# VibrationACQ.net
KiCad netlist of a schematic drawn in Altium Designer
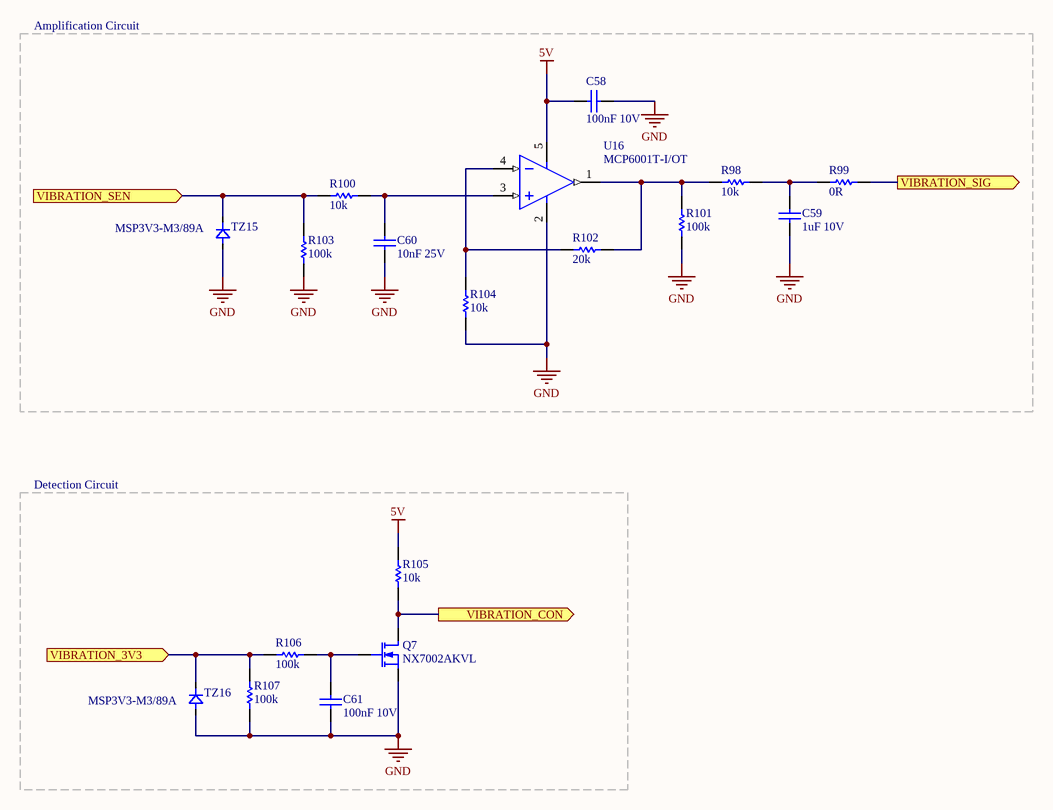
[diagram p0: VibrationACQ.SchDoc]

(export (version "E")
  (design (tool "Eeschema 10.0.6"))
  (components
    (comp (ref "C58")
      (value "100nF 10V")
      (footprint "0402")
      (description "Capacitor")
      (fields (field (name "PARTNUMBER") "CAP.100n.10V.20%.SMD.0402") (field (name "MANUFACTURER") "Wurth"))
      (libsource (lib "IntLib") (part "Cap"))
    )
    (comp (ref "C59")
      (value "1uF 10V")
      (footprint "C0805")
      (description "Capacitor")
      (fields (field (name "PARTNUMBER") "CAP.1u.10V.10%.SMD.0805") (field (name "MANUFACTURER") "Vishay"))
      (libsource (lib "IntLib") (part "Cap"))
    )
    (comp (ref "C60")
      (value "10nF 25V")
      (footprint "1608[0603]")
      (description "Capacitor")
      (fields (field (name "PARTNUMBER") "CAP.10n.25V.10%.SMD.0603") (field (name "MANUFACTURER") "Wurth"))
      (libsource (lib "IntLib") (part "Cap"))
    )
    (comp (ref "C61")
      (value "100nF 10V")
      (footprint "0402")
      (description "Capacitor")
      (fields (field (name "PARTNUMBER") "CAP.100n.10V.20%.SMD.0402") (field (name "MANUFACTURER") "Wurth"))
      (libsource (lib "IntLib") (part "Cap"))
    )
    (comp (ref "Q7")
      (value "NX7002AKVL")
      (footprint "SOT23_M")
      (description "Small Signal MOSFET 60 V, 310 mA, Single, N−Channel, SOT−23")
      (fields (field (name "MANUFACTURER") "Nexperia"))
      (libsource (lib "IntLib") (part "NX7002AKVL"))
    )
    (comp (ref "R98")
      (value "10k")
      (footprint "6-0805_M")
      (description "Resistor")
      (fields (field (name "PARTNUMBER") "RES.10K.1/8W.5%.SMD.0805") (field (name "MANUFACTURER") "Yageo"))
      (libsource (lib "IntLib") (part "Res"))
    )
    (comp (ref "R99")
      (value "0R")
      (footprint "6-0805_M")
      (description "Resistor")
      (fields (field (name "PARTNUMBER") "RES.0R.1/8W.5%.SMD.0805") (field (name "MANUFACTURER") "Vishay"))
      (libsource (lib "IntLib") (part "Res"))
    )
    (comp (ref "R100")
      (value "10k")
      (footprint "6-0805_M")
      (description "Resistor")
      (fields (field (name "PARTNUMBER") "RES.10K.1/8W.5%.SMD.0805") (field (name "MANUFACTURER") "Yageo"))
      (libsource (lib "IntLib") (part "Res"))
    )
    (comp (ref "R101")
      (value "100k")
      (footprint "6-0805_M")
      (description "Resistor")
      (fields (field (name "PARTNUMBER") "RES.100K.1/8W.5%.SMD.0805") (field (name "MANUFACTURER") "Yageo"))
      (libsource (lib "IntLib") (part "Res"))
    )
    (comp (ref "R102")
      (value "20k")
      (footprint "6-0805_M")
      (description "Resistor")
      (fields (field (name "PARTNUMBER") "RES.20K.1/8W.1%.SMD.0805") (field (name "MANUFACTURER") "Vishay"))
      (libsource (lib "IntLib") (part "Res"))
    )
    (comp (ref "R103")
      (value "100k")
      (footprint "6-0805_M")
      (description "Resistor")
      (fields (field (name "PARTNUMBER") "RES.100k.1/8W.5%.SMD.0805") (field (name "MANUFACTURER") "Bourns"))
      (libsource (lib "IntLib") (part "Res"))
    )
    (comp (ref "R104")
      (value "10k")
      (footprint "6-0805_M")
      (description "Resistor")
      (fields (field (name "PARTNUMBER") "RES.10K.1/8W.5%.SMD.0805") (field (name "MANUFACTURER") "Yageo"))
      (libsource (lib "IntLib") (part "Res"))
    )
    (comp (ref "R105")
      (value "10k")
      (footprint "6-0805_M")
      (description "Resistor")
      (fields (field (name "PARTNUMBER") "RES.10K.1/8W.5%.SMD.0805") (field (name "MANUFACTURER") "Yageo"))
      (libsource (lib "IntLib") (part "Res"))
    )
    (comp (ref "R106")
      (value "100k")
      (footprint "6-0805_M")
      (description "Resistor")
      (fields (field (name "PARTNUMBER") "RES.100K.1/8W.5%.SMD.0805") (field (name "MANUFACTURER") "Yageo"))
      (libsource (lib "IntLib") (part "Res"))
    )
    (comp (ref "R107")
      (value "100k")
      (footprint "6-0805_M")
      (description "Resistor")
      (fields (field (name "PARTNUMBER") "RES.100k.1/8W.5%.SMD.0805") (field (name "MANUFACTURER") "Bourns"))
      (libsource (lib "IntLib") (part "Res"))
    )
    (comp (ref "TZ15")
      (value "MSP3V3-M3/89A")
      (footprint "DO-219AD")
      (description "ESD Suppressors / TVS Diodes 100W 3.3V Unidirect")
      (fields (field (name "MANUFACTURER") "Vishay"))
      (libsource (lib "IntLib") (part "MSP3V3-M3/89A"))
    )
    (comp (ref "TZ16")
      (value "MSP3V3-M3/89A")
      (footprint "DO-219AD")
      (description "ESD Suppressors / TVS Diodes 100W 3.3V Unidirect")
      (fields (field (name "MANUFACTURER") "Vishay"))
      (libsource (lib "IntLib") (part "MSP3V3-M3/89A"))
    )
    (comp (ref "U16")
      (value "MCP6001T-I/OT")
      (footprint "SOT23-5")
      (description "Operational Amplifiers - Op Amps Single 1.8V 1MHz")
      (fields (field (name "MANUFACTURER") "Microchip"))
      (libsource (lib "IntLib") (part "MCP6001T-I/OT"))
    )
  )
  (nets
    (net (code "1") (name "/VIBRATION_3V3") (class "Default")
      (node (ref "R106") (pin "2") (pinfunction "2_2") (pintype "passive"))
      (node (ref "R107") (pin "1") (pinfunction "1_1") (pintype "passive"))
      (node (ref "TZ16") (pin "2") (pinfunction "C_2") (pintype "passive"))
    )
    (net (code "2") (name "/VIBRATION_CON") (class "Default")
      (node (ref "Q7") (pin "3") (pinfunction "D_3") (pintype "passive"))
      (node (ref "R105") (pin "1") (pinfunction "1_1") (pintype "passive"))
    )
    (net (code "3") (name "/VIBRATION_SEN") (class "Default")
      (node (ref "R100") (pin "1") (pinfunction "1_1") (pintype "passive"))
      (node (ref "R103") (pin "1") (pinfunction "1_1") (pintype "passive"))
      (node (ref "TZ15") (pin "2") (pinfunction "C_2") (pintype "passive"))
    )
    (net (code "4") (name "/VIBRATION_SIG") (class "Default")
      (node (ref "R99") (pin "1") (pinfunction "1_1") (pintype "passive"))
    )
    (net (code "5") (name "5V") (class "Default")
      (node (ref "C58") (pin "1") (pinfunction "1_1") (pintype "passive"))
      (node (ref "R105") (pin "2") (pinfunction "2_2") (pintype "passive"))
      (node (ref "U16") (pin "5") (pinfunction "V+_5") (pintype "power_in"))
    )
    (net (code "6") (name "GND") (class "Default")
      (node (ref "C58") (pin "2") (pinfunction "2_2") (pintype "passive"))
      (node (ref "C59") (pin "1") (pinfunction "1_1") (pintype "passive"))
      (node (ref "C60") (pin "1") (pinfunction "1_1") (pintype "passive"))
      (node (ref "C61") (pin "1") (pinfunction "1_1") (pintype "passive"))
      (node (ref "Q7") (pin "2") (pinfunction "S_2") (pintype "passive"))
      (node (ref "R101") (pin "1") (pinfunction "1_1") (pintype "passive"))
      (node (ref "R103") (pin "2") (pinfunction "2_2") (pintype "passive"))
      (node (ref "R104") (pin "1") (pinfunction "1_1") (pintype "passive"))
      (node (ref "R107") (pin "2") (pinfunction "2_2") (pintype "passive"))
      (node (ref "TZ15") (pin "1") (pinfunction "A_1") (pintype "passive"))
      (node (ref "TZ16") (pin "1") (pinfunction "A_1") (pintype "passive"))
      (node (ref "U16") (pin "2") (pinfunction "V-_2") (pintype "power_in"))
    )
    (net (code "7") (name "Net-(C59-Pad2)") (class "Default")
      (node (ref "C59") (pin "2") (pinfunction "2_2") (pintype "passive"))
      (node (ref "R98") (pin "1") (pinfunction "1_1") (pintype "passive"))
      (node (ref "R99") (pin "2") (pinfunction "2_2") (pintype "passive"))
    )
    (net (code "8") (name "Net-(Q7-G)") (class "Default")
      (node (ref "C61") (pin "2") (pinfunction "2_2") (pintype "passive"))
      (node (ref "Q7") (pin "1") (pinfunction "G_1") (pintype "passive"))
      (node (ref "R106") (pin "1") (pinfunction "1_1") (pintype "passive"))
    )
    (net (code "9") (name "Net-(U16-IN+)") (class "Default")
      (node (ref "C60") (pin "2") (pinfunction "2_2") (pintype "passive"))
      (node (ref "R100") (pin "2") (pinfunction "2_2") (pintype "passive"))
      (node (ref "U16") (pin "3") (pinfunction "IN+_3") (pintype "input"))
    )
    (net (code "10") (name "Net-(U16-IN-)") (class "Default")
      (node (ref "R102") (pin "1") (pinfunction "1_1") (pintype "passive"))
      (node (ref "R104") (pin "2") (pinfunction "2_2") (pintype "passive"))
      (node (ref "U16") (pin "4") (pinfunction "IN-_4") (pintype "input"))
    )
    (net (code "11") (name "Net-(U16-Out)") (class "Default")
      (node (ref "R101") (pin "2") (pinfunction "2_2") (pintype "passive"))
      (node (ref "R102") (pin "2") (pinfunction "2_2") (pintype "passive"))
      (node (ref "R98") (pin "2") (pinfunction "2_2") (pintype "passive"))
      (node (ref "U16") (pin "1") (pinfunction "Out_1") (pintype "output"))
    )
  )
)
